# design1.net
KiCad netlist of a schematic drawn in EAGLE
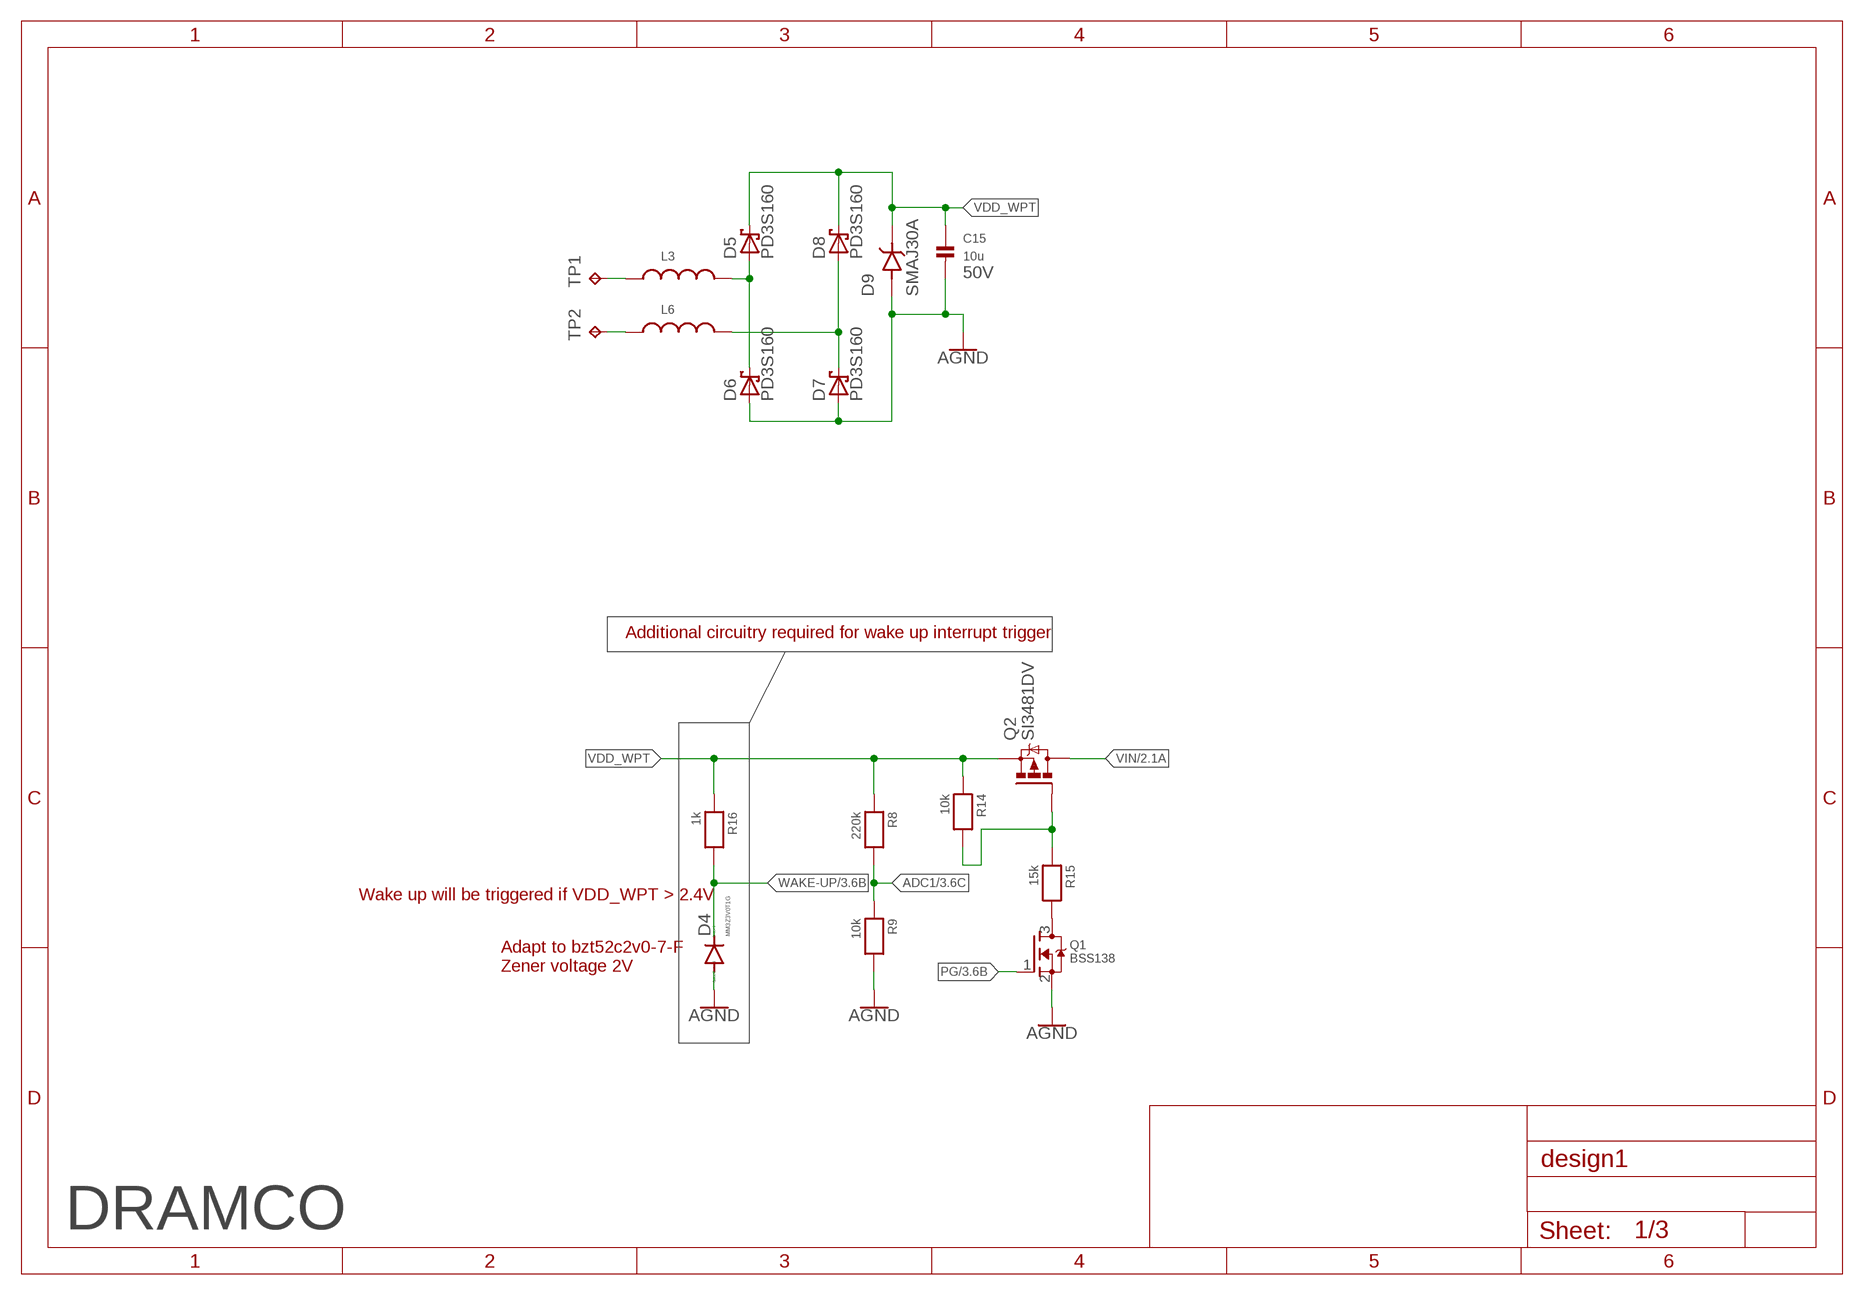
[diagram p0: schematic, sheet 1]
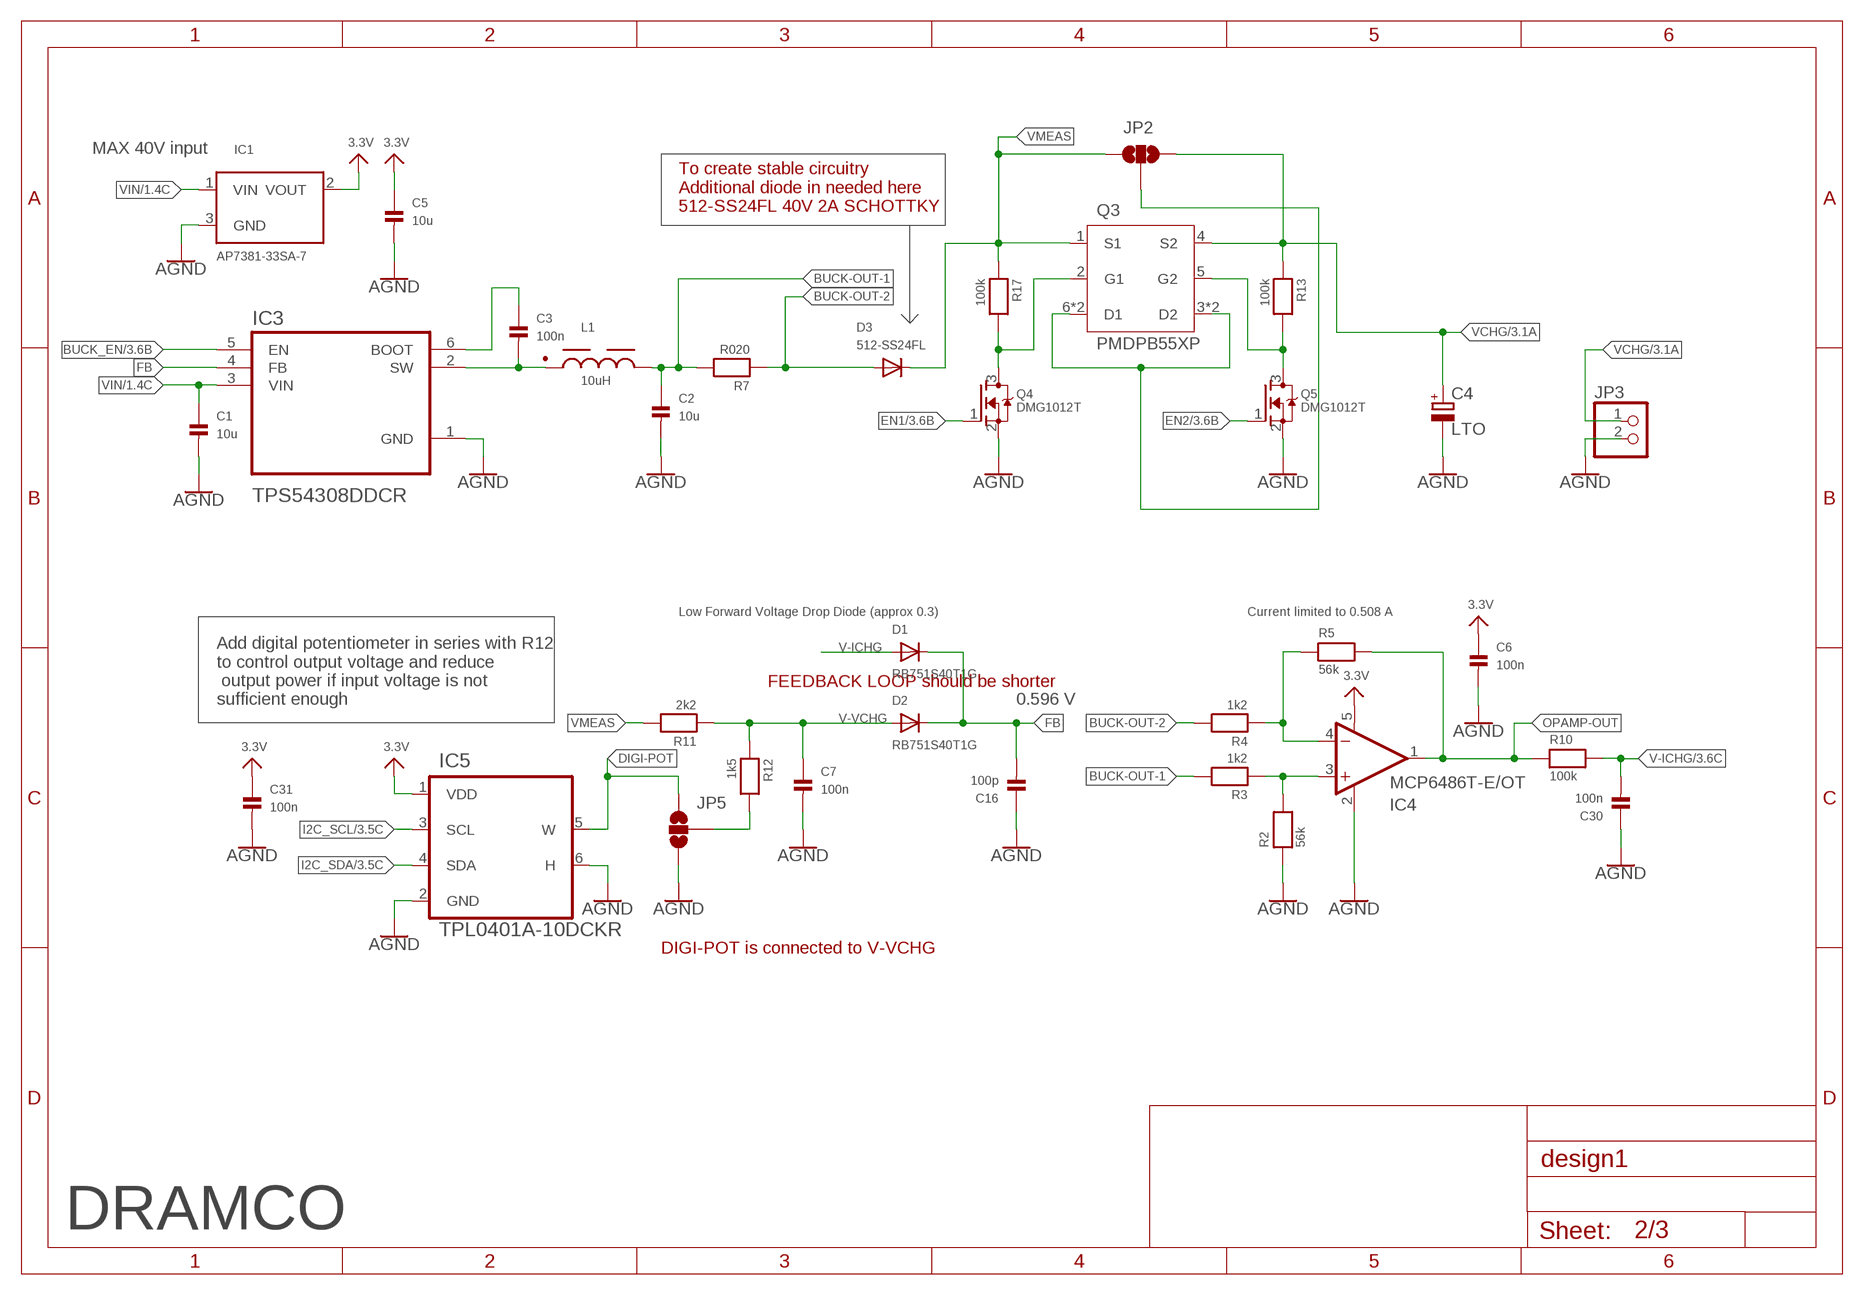
[diagram p1: schematic, sheet 2]
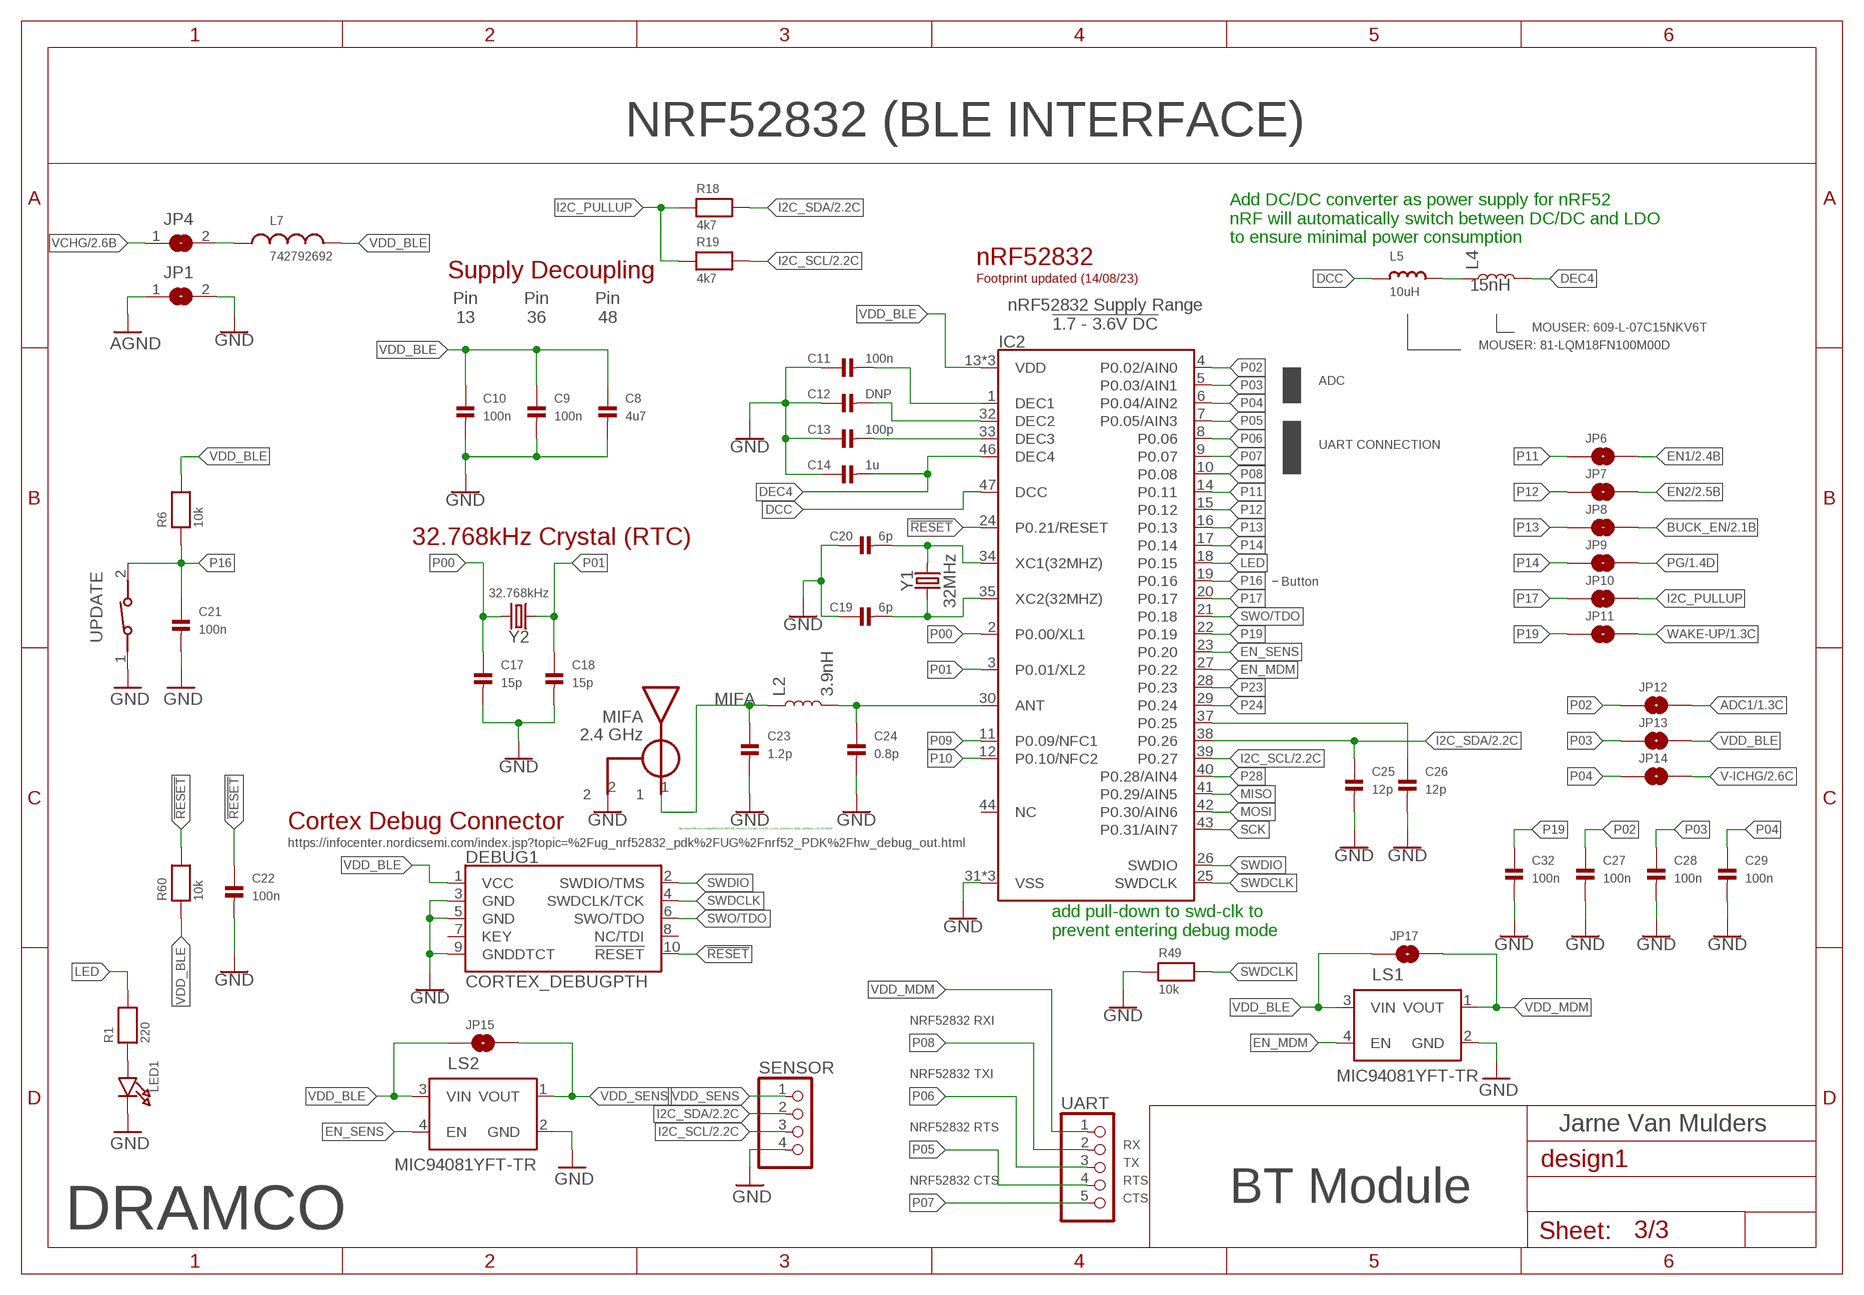
[diagram p2: schematic, sheet 3]

(export (version "E")
  (design (tool "Eeschema 10.0.6"))
  (components
    (comp (ref "C15")
      (value "10u")
      (footprint "eagle-import:1206")
      (libsource (lib "eagle-import") (part "CAP_CERAMIC1206"))
    )
    (comp (ref "D4")
      (value "MM3Z3V0T1G")
      (footprint "eagle-import:SOD323-R")
      (libsource (lib "eagle-import") (part "DIODE-SOD323-R"))
    )
    (comp (ref "D5")
      (value "PD3S160")
      (footprint "eagle-import:POWERDI323")
      (libsource (lib "eagle-import") (part "PD3S160"))
    )
    (comp (ref "D6")
      (value "PD3S160")
      (footprint "eagle-import:POWERDI323")
      (libsource (lib "eagle-import") (part "PD3S160"))
    )
    (comp (ref "D7")
      (value "PD3S160")
      (footprint "eagle-import:POWERDI323")
      (libsource (lib "eagle-import") (part "PD3S160"))
    )
    (comp (ref "D8")
      (value "PD3S160")
      (footprint "eagle-import:POWERDI323")
      (libsource (lib "eagle-import") (part "PD3S160"))
    )
    (comp (ref "D9")
      (value "SMAJ30A")
      (footprint "eagle-import:DIOM5026X229N")
      (fields (field (name "MF") "Littelfuse"))
      (libsource (lib "eagle-import") (part "SMAJ30A"))
    )
    (comp (ref "L3")
      (value "WE-CAIR_4248_744912182")
      (footprint "eagle-import:WE-CAIR_4248")
      (libsource (lib "eagle-import") (part "WE-CAIR_4248_744912182"))
    )
    (comp (ref "L6")
      (value "WE-CAIR_4248_744912182")
      (footprint "eagle-import:WE-CAIR_4248")
      (libsource (lib "eagle-import") (part "WE-CAIR_4248_744912182"))
    )
    (comp (ref "Q1")
      (value "BSS138")
      (footprint "eagle-import:SOT23-R")
      (libsource (lib "eagle-import") (part "MOSFET-NREFLOW"))
    )
    (comp (ref "Q2")
      (value "SI3481DV")
      (footprint "eagle-import:TSOP-6.PAC")
      (libsource (lib "eagle-import") (part "SI3481DV"))
    )
    (comp (ref "R8")
      (value "220k")
      (footprint "eagle-import:0603")
      (libsource (lib "eagle-import") (part "RESISTOR0603"))
    )
    (comp (ref "R9")
      (value "10k")
      (footprint "eagle-import:0603")
      (libsource (lib "eagle-import") (part "RESISTOR0603"))
    )
    (comp (ref "R14")
      (value "10k")
      (footprint "eagle-import:0603")
      (libsource (lib "eagle-import") (part "RESISTOR0603"))
    )
    (comp (ref "R15")
      (value "15k")
      (footprint "eagle-import:0603")
      (libsource (lib "eagle-import") (part "RESISTOR0603"))
    )
    (comp (ref "R16")
      (value "1k")
      (footprint "eagle-import:0603")
      (libsource (lib "eagle-import") (part "RESISTOR0603"))
    )
    (comp (ref "TP1")
      (value "TPTP20SQ")
      (footprint "eagle-import:TP20SQ")
      (libsource (lib "eagle-import") (part "TPTP20SQ"))
    )
    (comp (ref "TP2")
      (value "TPTP20SQ")
      (footprint "eagle-import:TP20SQ")
      (libsource (lib "eagle-import") (part "TPTP20SQ"))
    )
    (comp (ref "C1")
      (value "10u")
      (footprint "eagle-import:0603")
      (libsource (lib "eagle-import") (part "CAP_CERAMIC0603"))
    )
    (comp (ref "C2")
      (value "10u")
      (footprint "eagle-import:0603")
      (libsource (lib "eagle-import") (part "CAP_CERAMIC0603"))
    )
    (comp (ref "C3")
      (value "100n")
      (footprint "eagle-import:0603")
      (libsource (lib "eagle-import") (part "CAP_CERAMIC0603"))
    )
    (comp (ref "C4")
      (value "LTO")
      (footprint "eagle-import:E5-10,5")
      (libsource (lib "eagle-import") (part "CPOL-EUE5-10.5"))
    )
    (comp (ref "C5")
      (value "10u")
      (footprint "eagle-import:0603")
      (libsource (lib "eagle-import") (part "CAP_CERAMIC0603"))
    )
    (comp (ref "C6")
      (value "100n")
      (footprint "eagle-import:0402")
      (libsource (lib "eagle-import") (part "CAP_CERAMIC0402"))
    )
    (comp (ref "C7")
      (value "100n")
      (footprint "eagle-import:0603")
      (libsource (lib "eagle-import") (part "CAP_CERAMIC0603"))
    )
    (comp (ref "C16")
      (value "100p")
      (footprint "eagle-import:0603")
      (libsource (lib "eagle-import") (part "CAP_CERAMIC0603"))
    )
    (comp (ref "C30")
      (value "100n")
      (footprint "eagle-import:0603")
      (libsource (lib "eagle-import") (part "CAP_CERAMIC0603"))
    )
    (comp (ref "C31")
      (value "100n")
      (footprint "eagle-import:0402")
      (libsource (lib "eagle-import") (part "CAP_CERAMIC0402"))
    )
    (comp (ref "D1")
      (value "RB751S40T1G")
      (footprint "eagle-import:SOD-523")
      (libsource (lib "eagle-import") (part "DIODESOD-523"))
    )
    (comp (ref "D2")
      (value "RB751S40T1G")
      (footprint "eagle-import:SOD-523")
      (libsource (lib "eagle-import") (part "DIODESOD-523"))
    )
    (comp (ref "D3")
      (value "512-SS24FL")
      (footprint "eagle-import:SOD-123")
      (libsource (lib "eagle-import") (part "DIODESOD-123"))
    )
    (comp (ref "IC1")
      (value "AP7381-33SA-7")
      (footprint "eagle-import:SOT23-R")
      (libsource (lib "eagle-import") (part "VREG_SOT23"))
    )
    (comp (ref "IC3")
      (value "TPS54308DDCR")
      (footprint "eagle-import:SOT95P280X110-6N")
      (fields (field (name "MF") "Texas Instruments"))
      (libsource (lib "eagle-import") (part "TPS54308DDCR"))
    )
    (comp (ref "IC4")
      (value "MCP6486T-E/OT")
      (footprint "eagle-import:SOT23-5")
      (libsource (lib "eagle-import") (part "MCP6291T-E/OT"))
    )
    (comp (ref "IC5")
      (value "TPL0401A-10DCKR")
      (footprint "eagle-import:SOT65P210X110-6N")
      (fields (field (name "MF") "Texas Instruments"))
      (libsource (lib "eagle-import") (part "TPL0401A-10DCKR"))
    )
    (comp (ref "JP2")
      (value "JUMPER-SMT_3_NO_NO-SILK")
      (footprint "eagle-import:SMT-JUMPER_3_NO_NO-SILK")
      (libsource (lib "eagle-import") (part "JUMPER-SMT_3_NO_NO-SILK"))
    )
    (comp (ref "JP3")
      (value "HEADER-1X2ROUND")
      (footprint "eagle-import:1X02_ROUND")
      (libsource (lib "eagle-import") (part "HEADER-1X2ROUND"))
    )
    (comp (ref "JP5")
      (value "JUMPER-SMT_3_NO_NO-SILK")
      (footprint "eagle-import:SMT-JUMPER_3_NO_NO-SILK")
      (libsource (lib "eagle-import") (part "JUMPER-SMT_3_NO_NO-SILK"))
    )
    (comp (ref "L1")
      (value "10uH")
      (footprint "eagle-import:WE-PD_7332_7345_PLASTIC_BASE")
      (libsource (lib "eagle-import") (part "WE-PD_7332_PLASTIC_7447789127"))
    )
    (comp (ref "Q3")
      (value "PMDPB55XP")
      (footprint "eagle-import:SON65P200X200X65-8N")
      (libsource (lib "eagle-import") (part "PMDPB55XP"))
    )
    (comp (ref "Q4")
      (value "DMG1012T")
      (footprint "eagle-import:SOT523-3")
      (libsource (lib "eagle-import") (part "DMG1012T"))
    )
    (comp (ref "Q5")
      (value "DMG1012T")
      (footprint "eagle-import:SOT523-3")
      (libsource (lib "eagle-import") (part "DMG1012T"))
    )
    (comp (ref "R2")
      (value "56k")
      (footprint "eagle-import:0603")
      (libsource (lib "eagle-import") (part "RESISTOR0603"))
    )
    (comp (ref "R3")
      (value "1k2")
      (footprint "eagle-import:0603")
      (libsource (lib "eagle-import") (part "RESISTOR0603"))
    )
    (comp (ref "R4")
      (value "1k2")
      (footprint "eagle-import:0603")
      (libsource (lib "eagle-import") (part "RESISTOR0603"))
    )
    (comp (ref "R5")
      (value "56k")
      (footprint "eagle-import:0603")
      (libsource (lib "eagle-import") (part "RESISTOR0603"))
    )
    (comp (ref "R7")
      (value "R020")
      (footprint "eagle-import:0603")
      (libsource (lib "eagle-import") (part "RESISTOR0603"))
    )
    (comp (ref "R10")
      (value "100k")
      (footprint "eagle-import:0603")
      (libsource (lib "eagle-import") (part "RESISTOR0603"))
    )
    (comp (ref "R11")
      (value "2k2")
      (footprint "eagle-import:0603")
      (libsource (lib "eagle-import") (part "RESISTOR0603"))
    )
    (comp (ref "R12")
      (value "1k5")
      (footprint "eagle-import:0603")
      (libsource (lib "eagle-import") (part "RESISTOR0603"))
    )
    (comp (ref "R13")
      (value "100k")
      (footprint "eagle-import:0402")
      (libsource (lib "eagle-import") (part "RESISTOR0402"))
    )
    (comp (ref "R17")
      (value "100k")
      (footprint "eagle-import:0402")
      (libsource (lib "eagle-import") (part "RESISTOR0402"))
    )
    (comp (ref "C8")
      (value "4u7")
      (footprint "eagle-import:0603")
      (libsource (lib "eagle-import") (part "CAP_CERAMIC0603"))
    )
    (comp (ref "C9")
      (value "100n")
      (footprint "eagle-import:0402")
      (libsource (lib "eagle-import") (part "CAP_CERAMIC0402"))
    )
    (comp (ref "C10")
      (value "100n")
      (footprint "eagle-import:0402")
      (libsource (lib "eagle-import") (part "CAP_CERAMIC0402"))
    )
    (comp (ref "C11")
      (value "100n")
      (footprint "eagle-import:0402")
      (libsource (lib "eagle-import") (part "CAP_CERAMIC0402"))
    )
    (comp (ref "C12")
      (value "DNP")
      (footprint "eagle-import:0402")
      (libsource (lib "eagle-import") (part "CAP_CERAMIC0402"))
    )
    (comp (ref "C13")
      (value "100p")
      (footprint "eagle-import:0402")
      (libsource (lib "eagle-import") (part "CAP_CERAMIC0402"))
    )
    (comp (ref "C14")
      (value "1u")
      (footprint "eagle-import:0402")
      (libsource (lib "eagle-import") (part "CAP_CERAMIC0402"))
    )
    (comp (ref "C17")
      (value "15p")
      (footprint "eagle-import:0402")
      (libsource (lib "eagle-import") (part "CAP_CERAMIC0402"))
    )
    (comp (ref "C18")
      (value "15p")
      (footprint "eagle-import:0402")
      (libsource (lib "eagle-import") (part "CAP_CERAMIC0402"))
    )
    (comp (ref "C19")
      (value "6p")
      (footprint "eagle-import:0402")
      (libsource (lib "eagle-import") (part "CAP_CERAMIC0402"))
    )
    (comp (ref "C20")
      (value "6p")
      (footprint "eagle-import:0402")
      (libsource (lib "eagle-import") (part "CAP_CERAMIC0402"))
    )
    (comp (ref "C21")
      (value "100n")
      (footprint "eagle-import:0402")
      (libsource (lib "eagle-import") (part "CAP_CERAMIC0402"))
    )
    (comp (ref "C22")
      (value "100n")
      (footprint "eagle-import:0402")
      (libsource (lib "eagle-import") (part "CAP_CERAMIC0402"))
    )
    (comp (ref "C23")
      (value "1.2p")
      (footprint "eagle-import:0402")
      (libsource (lib "eagle-import") (part "CAP_CERAMIC0402"))
    )
    (comp (ref "C24")
      (value "0.8p")
      (footprint "eagle-import:0402")
      (libsource (lib "eagle-import") (part "CAP_CERAMIC0402"))
    )
    (comp (ref "C25")
      (value "12p")
      (footprint "eagle-import:0402")
      (libsource (lib "eagle-import") (part "CAP_CERAMIC0402"))
    )
    (comp (ref "C26")
      (value "12p")
      (footprint "eagle-import:0402")
      (libsource (lib "eagle-import") (part "CAP_CERAMIC0402"))
    )
    (comp (ref "C27")
      (value "100n")
      (footprint "eagle-import:0402")
      (libsource (lib "eagle-import") (part "CAP_CERAMIC0402"))
    )
    (comp (ref "C28")
      (value "100n")
      (footprint "eagle-import:0402")
      (libsource (lib "eagle-import") (part "CAP_CERAMIC0402"))
    )
    (comp (ref "C29")
      (value "100n")
      (footprint "eagle-import:0402")
      (libsource (lib "eagle-import") (part "CAP_CERAMIC0402"))
    )
    (comp (ref "C32")
      (value "100n")
      (footprint "eagle-import:0402")
      (libsource (lib "eagle-import") (part "CAP_CERAMIC0402"))
    )
    (comp (ref "DEBUG1")
      (value "CORTEX_DEBUGPTH")
      (footprint "eagle-import:2X5-PTH-1.27MM")
      (libsource (lib "eagle-import") (part "CORTEX_DEBUGPTH"))
    )
    (comp (ref "IC2")
      (value "NRF52832-EXTENDED")
      (footprint "eagle-import:QFN48-6X6MM-EXTENDED")
      (libsource (lib "eagle-import") (part "NRF52832-EXTENDED"))
    )
    (comp (ref "JP1")
      (value "SOLDERJUMPERREFLOW_NOPASTE")
      (footprint "eagle-import:SOLDERJUMPER_REFLOW_NOPASTE")
      (libsource (lib "eagle-import") (part "SOLDERJUMPERREFLOW_NOPASTE"))
    )
    (comp (ref "JP4")
      (value "SOLDERJUMPERREFLOW_NOPASTE")
      (footprint "eagle-import:SOLDERJUMPER_REFLOW_NOPASTE")
      (libsource (lib "eagle-import") (part "SOLDERJUMPERREFLOW_NOPASTE"))
    )
    (comp (ref "JP6")
      (value "JUMPER-SMT_2_NO_NO-SILK")
      (footprint "eagle-import:SMT-JUMPER_2_NO_NO-SILK")
      (libsource (lib "eagle-import") (part "JUMPER-SMT_2_NO_NO-SILK"))
    )
    (comp (ref "JP7")
      (value "JUMPER-SMT_2_NO_NO-SILK")
      (footprint "eagle-import:SMT-JUMPER_2_NO_NO-SILK")
      (libsource (lib "eagle-import") (part "JUMPER-SMT_2_NO_NO-SILK"))
    )
    (comp (ref "JP8")
      (value "JUMPER-SMT_2_NO_NO-SILK")
      (footprint "eagle-import:SMT-JUMPER_2_NO_NO-SILK")
      (libsource (lib "eagle-import") (part "JUMPER-SMT_2_NO_NO-SILK"))
    )
    (comp (ref "JP9")
      (value "JUMPER-SMT_2_NO_NO-SILK")
      (footprint "eagle-import:SMT-JUMPER_2_NO_NO-SILK")
      (libsource (lib "eagle-import") (part "JUMPER-SMT_2_NO_NO-SILK"))
    )
    (comp (ref "JP10")
      (value "JUMPER-SMT_2_NO_NO-SILK")
      (footprint "eagle-import:SMT-JUMPER_2_NO_NO-SILK")
      (libsource (lib "eagle-import") (part "JUMPER-SMT_2_NO_NO-SILK"))
    )
    (comp (ref "JP11")
      (value "JUMPER-SMT_2_NO_NO-SILK")
      (footprint "eagle-import:SMT-JUMPER_2_NO_NO-SILK")
      (libsource (lib "eagle-import") (part "JUMPER-SMT_2_NO_NO-SILK"))
    )
    (comp (ref "JP12")
      (value "JUMPER-SMT_2_NO_NO-SILK")
      (footprint "eagle-import:SMT-JUMPER_2_NO_NO-SILK")
      (libsource (lib "eagle-import") (part "JUMPER-SMT_2_NO_NO-SILK"))
    )
    (comp (ref "JP13")
      (value "JUMPER-SMT_2_NO_NO-SILK")
      (footprint "eagle-import:SMT-JUMPER_2_NO_NO-SILK")
      (libsource (lib "eagle-import") (part "JUMPER-SMT_2_NO_NO-SILK"))
    )
    (comp (ref "JP14")
      (value "JUMPER-SMT_2_NO_NO-SILK")
      (footprint "eagle-import:SMT-JUMPER_2_NO_NO-SILK")
      (libsource (lib "eagle-import") (part "JUMPER-SMT_2_NO_NO-SILK"))
    )
    (comp (ref "JP15")
      (value "JUMPER-SMT_2_NO_NO-SILK")
      (footprint "eagle-import:SMT-JUMPER_2_NO_NO-SILK")
      (libsource (lib "eagle-import") (part "JUMPER-SMT_2_NO_NO-SILK"))
    )
    (comp (ref "JP17")
      (value "JUMPER-SMT_2_NO_NO-SILK")
      (footprint "eagle-import:SMT-JUMPER_2_NO_NO-SILK")
      (libsource (lib "eagle-import") (part "JUMPER-SMT_2_NO_NO-SILK"))
    )
    (comp (ref "L2")
      (value "3.9nH")
      (footprint "eagle-import:0402")
      (libsource (lib "eagle-import") (part "INDUCTOR-0402-3.9NH"))
    )
    (comp (ref "L4")
      (value "15nH")
      (footprint "eagle-import:0402")
      (libsource (lib "eagle-import") (part "INDUCTOR-0402-3.9NH"))
    )
    (comp (ref "L5")
      (value "10uH")
      (footprint "eagle-import:_0603MP")
      (libsource (lib "eagle-import") (part "INDUCTOR_0603MP"))
    )
    (comp (ref "L7")
      (value "742792692")
      (footprint "eagle-import:WE-CBF_0603(W=2.2)")
      (libsource (lib "eagle-import") (part "WE-CBF_0603_WB_HS_742792692"))
    )
    (comp (ref "LED1")
      (value "LED0805")
      (footprint "eagle-import:CHIPLED_0805")
      (libsource (lib "eagle-import") (part "LED0805"))
    )
    (comp (ref "LS1")
      (value "MIC94081YFT-TR")
      (footprint "eagle-import:IC_MIC94081YFT-TR")
      (fields (field (name "MF") "Microchip"))
      (libsource (lib "eagle-import") (part "MIC94081YFT-TR"))
    )
    (comp (ref "LS2")
      (value "MIC94081YFT-TR")
      (footprint "eagle-import:IC_MIC94081YFT-TR")
      (fields (field (name "MF") "Microchip"))
      (libsource (lib "eagle-import") (part "MIC94081YFT-TR"))
    )
    (comp (ref "R1")
      (value "220")
      (footprint "eagle-import:0603")
      (libsource (lib "eagle-import") (part "RESISTOR0603"))
    )
    (comp (ref "R6")
      (value "10k")
      (footprint "eagle-import:0402")
      (libsource (lib "eagle-import") (part "RESISTOR0402"))
    )
    (comp (ref "R18")
      (value "4k7")
      (footprint "eagle-import:0402")
      (libsource (lib "eagle-import") (part "RESISTOR0402"))
    )
    (comp (ref "R19")
      (value "4k7")
      (footprint "eagle-import:0402")
      (libsource (lib "eagle-import") (part "RESISTOR0402"))
    )
    (comp (ref "R49")
      (value "10k")
      (footprint "eagle-import:0402")
      (libsource (lib "eagle-import") (part "RESISTOR0402"))
    )
    (comp (ref "R60")
      (value "10k")
      (footprint "eagle-import:0402")
      (libsource (lib "eagle-import") (part "RESISTOR0402"))
    )
    (comp (ref "SENSOR")
      (value "HEADER-1X4ROUND")
      (footprint "eagle-import:1X04_ROUND")
      (libsource (lib "eagle-import") (part "HEADER-1X4ROUND"))
    )
    (comp (ref "U$18")
      (value "BLE-ANT")
      (footprint "eagle-import:ANT-2G4")
      (libsource (lib "eagle-import") (part "BLE-ANT"))
    )
    (comp (ref "UART")
      (value "HEADER-1X5ROUND")
      (footprint "eagle-import:1X05_ROUND")
      (libsource (lib "eagle-import") (part "HEADER-1X5ROUND"))
    )
    (comp (ref "UPDATE")
      (value "434111043826")
      (footprint "eagle-import:434111043826")
      (libsource (lib "eagle-import") (part "434111043826"))
    )
    (comp (ref "Y1")
      (value "32MHz")
      (footprint "eagle-import:CRYSTAL-SMD-2.0X1.6MM")
      (libsource (lib "eagle-import") (part "CRYSTAL-32MHZ-SMD-2.0X1.6MM"))
    )
    (comp (ref "Y2")
      (value "32.768kHz")
      (footprint "eagle-import:CRYSTAL-SMD-3.2X1.5MM")
      (libsource (lib "eagle-import") (part "CRYSTAL-32.768KHZSMD-3.2X1.5"))
    )
  )
  (nets
    (net (code "1") (name "3.3V") (class "Default")
      (node (ref "C31") (pin "1") (pinfunction "P$1_1") (pintype "passive"))
      (node (ref "C5") (pin "1") (pinfunction "P$1_1") (pintype "passive"))
      (node (ref "C6") (pin "1") (pinfunction "P$1_1") (pintype "passive"))
      (node (ref "IC1") (pin "2") (pinfunction "VOUT_2") (pintype "power_in"))
      (node (ref "IC4") (pin "5") (pinfunction "V+_5") (pintype "power_in"))
      (node (ref "IC5") (pin "1") (pinfunction "VDD_1") (pintype "power_in"))
    )
    (net (code "2") (name "ADC1") (class "Default")
      (node (ref "JP12") (pin "2") (pinfunction "2_2") (pintype "passive"))
      (node (ref "R8") (pin "2") (pinfunction "2_2") (pintype "passive"))
      (node (ref "R9") (pin "1") (pinfunction "1_1") (pintype "passive"))
    )
    (net (code "3") (name "AGND") (class "Default")
      (node (ref "C1") (pin "2") (pinfunction "P$2_2") (pintype "passive"))
      (node (ref "C15") (pin "2") (pinfunction "P$2_2") (pintype "passive"))
      (node (ref "C16") (pin "1") (pinfunction "P$1_1") (pintype "passive"))
      (node (ref "C2") (pin "2") (pinfunction "P$2_2") (pintype "passive"))
      (node (ref "C30") (pin "1") (pinfunction "P$1_1") (pintype "passive"))
      (node (ref "C31") (pin "2") (pinfunction "P$2_2") (pintype "passive"))
      (node (ref "C4") (pin "-") (pinfunction "-_-") (pintype "passive"))
      (node (ref "C5") (pin "2") (pinfunction "P$2_2") (pintype "passive"))
      (node (ref "C6") (pin "2") (pinfunction "P$2_2") (pintype "passive"))
      (node (ref "C7") (pin "2") (pinfunction "P$2_2") (pintype "passive"))
      (node (ref "D4") (pin "A") (pinfunction "A_A") (pintype "passive"))
      (node (ref "D6") (pin "A") (pinfunction "A_A") (pintype "passive"))
      (node (ref "D7") (pin "A") (pinfunction "A_A") (pintype "passive"))
      (node (ref "D9") (pin "A") (pinfunction "A_A") (pintype "passive"))
      (node (ref "IC1") (pin "3") (pinfunction "GND_3") (pintype "power_in"))
      (node (ref "IC3") (pin "1") (pinfunction "GND_1") (pintype "power_in"))
      (node (ref "IC4") (pin "2") (pinfunction "V-_2") (pintype "power_in"))
      (node (ref "IC5") (pin "2") (pinfunction "GND_2") (pintype "power_in"))
      (node (ref "IC5") (pin "6") (pinfunction "H_6") (pintype "bidirectional"))
      (node (ref "JP1") (pin "1") (pinfunction "1_1") (pintype "passive"))
      (node (ref "JP3") (pin "2") (pinfunction "2_2") (pintype "passive"))
      (node (ref "JP5") (pin "1") (pinfunction "1_1") (pintype "passive"))
      (node (ref "Q1") (pin "2") (pinfunction "S_2") (pintype "bidirectional"))
      (node (ref "Q4") (pin "2") (pinfunction "S_2") (pintype "bidirectional"))
      (node (ref "Q5") (pin "2") (pinfunction "S_2") (pintype "bidirectional"))
      (node (ref "R2") (pin "1") (pinfunction "1_1") (pintype "passive"))
      (node (ref "R9") (pin "2") (pinfunction "2_2") (pintype "passive"))
    )
    (net (code "4") (name "BUCK-OUT-1") (class "Default")
      (node (ref "C2") (pin "1") (pinfunction "P$1_1") (pintype "passive"))
      (node (ref "L1") (pin "2") (pinfunction "2_2") (pintype "passive"))
      (node (ref "R3") (pin "2") (pinfunction "2_2") (pintype "passive"))
      (node (ref "R7") (pin "2") (pinfunction "2_2") (pintype "passive"))
    )
    (net (code "5") (name "BUCK-OUT-2") (class "Default")
      (node (ref "D3") (pin "A") (pinfunction "A_A") (pintype "passive"))
      (node (ref "R4") (pin "2") (pinfunction "2_2") (pintype "passive"))
      (node (ref "R7") (pin "1") (pinfunction "1_1") (pintype "passive"))
    )
    (net (code "6") (name "BUCK_EN") (class "Default")
      (node (ref "IC3") (pin "5") (pinfunction "EN_5") (pintype "input"))
      (node (ref "JP8") (pin "2") (pinfunction "2_2") (pintype "passive"))
    )
    (net (code "7") (name "DCC") (class "Default")
      (node (ref "IC2") (pin "47") (pinfunction "DCC_47") (pintype "bidirectional"))
      (node (ref "L5") (pin "1") (pinfunction "1_1") (pintype "passive"))
    )
    (net (code "8") (name "DEC4") (class "Default")
      (node (ref "C14") (pin "2") (pinfunction "P$2_2") (pintype "passive"))
      (node (ref "IC2") (pin "46") (pinfunction "DEC4_46") (pintype "bidirectional"))
      (node (ref "L4") (pin "2") (pinfunction "2_2") (pintype "passive"))
    )
    (net (code "9") (name "DIGI-POT") (class "Default")
      (node (ref "IC5") (pin "5") (pinfunction "W_5") (pintype "bidirectional"))
      (node (ref "JP5") (pin "3") (pinfunction "3_3") (pintype "passive"))
    )
    (net (code "10") (name "EN1") (class "Default")
      (node (ref "JP6") (pin "2") (pinfunction "2_2") (pintype "passive"))
      (node (ref "Q4") (pin "1") (pinfunction "G_1") (pintype "bidirectional"))
    )
    (net (code "11") (name "EN2") (class "Default")
      (node (ref "JP7") (pin "2") (pinfunction "2_2") (pintype "passive"))
      (node (ref "Q5") (pin "1") (pinfunction "G_1") (pintype "bidirectional"))
    )
    (net (code "12") (name "EN_MDM") (class "Default")
      (node (ref "IC2") (pin "27") (pinfunction "P0.22_27") (pintype "bidirectional"))
      (node (ref "LS1") (pin "4") (pinfunction "EN_4") (pintype "input"))
    )
    (net (code "13") (name "EN_SENS") (class "Default")
      (node (ref "IC2") (pin "23") (pinfunction "P0.20_23") (pintype "bidirectional"))
      (node (ref "LS2") (pin "4") (pinfunction "EN_4") (pintype "input"))
    )
    (net (code "14") (name "FB") (class "Default")
      (node (ref "C16") (pin "2") (pinfunction "P$2_2") (pintype "passive"))
      (node (ref "D1") (pin "K") (pinfunction "C_K") (pintype "passive"))
      (node (ref "D2") (pin "K") (pinfunction "C_K") (pintype "passive"))
      (node (ref "IC3") (pin "4") (pinfunction "FB_4") (pintype "input"))
    )
    (net (code "15") (name "GND") (class "Default")
      (node (ref "C10") (pin "2") (pinfunction "P$2_2") (pintype "passive"))
      (node (ref "C11") (pin "1") (pinfunction "P$1_1") (pintype "passive"))
      (node (ref "C12") (pin "1") (pinfunction "P$1_1") (pintype "passive"))
      (node (ref "C13") (pin "1") (pinfunction "P$1_1") (pintype "passive"))
      (node (ref "C14") (pin "1") (pinfunction "P$1_1") (pintype "passive"))
      (node (ref "C17") (pin "2") (pinfunction "P$2_2") (pintype "passive"))
      (node (ref "C18") (pin "2") (pinfunction "P$2_2") (pintype "passive"))
      (node (ref "C19") (pin "1") (pinfunction "P$1_1") (pintype "passive"))
      (node (ref "C20") (pin "1") (pinfunction "P$1_1") (pintype "passive"))
      (node (ref "C21") (pin "2") (pinfunction "P$2_2") (pintype "passive"))
      (node (ref "C22") (pin "2") (pinfunction "P$2_2") (pintype "passive"))
      (node (ref "C23") (pin "2") (pinfunction "P$2_2") (pintype "passive"))
      (node (ref "C24") (pin "2") (pinfunction "P$2_2") (pintype "passive"))
      (node (ref "C25") (pin "2") (pinfunction "P$2_2") (pintype "passive"))
      (node (ref "C26") (pin "2") (pinfunction "P$2_2") (pintype "passive"))
      (node (ref "C27") (pin "2") (pinfunction "P$2_2") (pintype "passive"))
      (node (ref "C28") (pin "2") (pinfunction "P$2_2") (pintype "passive"))
      (node (ref "C29") (pin "2") (pinfunction "P$2_2") (pintype "passive"))
      (node (ref "C32") (pin "2") (pinfunction "P$2_2") (pintype "passive"))
      (node (ref "C8") (pin "2") (pinfunction "P$2_2") (pintype "passive"))
      (node (ref "C9") (pin "2") (pinfunction "P$2_2") (pintype "passive"))
      (node (ref "DEBUG1") (pin "3") (pinfunction "GND_3") (pintype "bidirectional"))
      (node (ref "DEBUG1") (pin "5") (pinfunction "GND_5") (pintype "bidirectional"))
      (node (ref "DEBUG1") (pin "9") (pinfunction "GNDDTCT_9") (pintype "bidirectional"))
      (node (ref "IC2") (pin "31") (pinfunction "VSS_31") (pintype "bidirectional"))
      (node (ref "IC2") (pin "45") (pinfunction "VSS_45") (pintype "bidirectional"))
      (node (ref "IC2") (pin "EP") (pinfunction "VSS_EP") (pintype "bidirectional"))
      (node (ref "JP1") (pin "2") (pinfunction "2_2") (pintype "passive"))
      (node (ref "LED1") (pin "C") (pinfunction "C_C") (pintype "passive"))
      (node (ref "LS1") (pin "2") (pinfunction "GND_2") (pintype "power_in"))
      (node (ref "LS2") (pin "2") (pinfunction "GND_2") (pintype "power_in"))
      (node (ref "R49") (pin "1") (pinfunction "1_1") (pintype "passive"))
      (node (ref "SENSOR") (pin "4") (pinfunction "4_4") (pintype "passive"))
      (node (ref "U$18") (pin "2") (pinfunction "2_2") (pintype "bidirectional"))
      (node (ref "UPDATE") (pin "1") (pinfunction "1_1") (pintype "passive"))
    )
    (net (code "16") (name "I2C_PULLUP") (class "Default")
      (node (ref "JP10") (pin "2") (pinfunction "2_2") (pintype "passive"))
      (node (ref "R18") (pin "1") (pinfunction "1_1") (pintype "passive"))
      (node (ref "R19") (pin "1") (pinfunction "1_1") (pintype "passive"))
    )
    (net (code "17") (name "I2C_SCL") (class "Default")
      (node (ref "IC2") (pin "39") (pinfunction "P0.27_39") (pintype "bidirectional"))
      (node (ref "IC5") (pin "3") (pinfunction "SCL_3") (pintype "bidirectional"))
      (node (ref "R19") (pin "2") (pinfunction "2_2") (pintype "passive"))
      (node (ref "SENSOR") (pin "3") (pinfunction "3_3") (pintype "passive"))
    )
    (net (code "18") (name "I2C_SDA") (class "Default")
      (node (ref "C25") (pin "1") (pinfunction "P$1_1") (pintype "passive"))
      (node (ref "IC2") (pin "38") (pinfunction "P0.26_38") (pintype "bidirectional"))
      (node (ref "IC5") (pin "4") (pinfunction "SDA_4") (pintype "bidirectional"))
      (node (ref "R18") (pin "2") (pinfunction "2_2") (pintype "passive"))
      (node (ref "SENSOR") (pin "2") (pinfunction "2_2") (pintype "passive"))
    )
    (net (code "19") (name "LED") (class "Default")
      (node (ref "IC2") (pin "18") (pinfunction "P0.15_18") (pintype "bidirectional"))
      (node (ref "R1") (pin "2") (pinfunction "2_2") (pintype "passive"))
    )
    (net (code "20") (name "MIFA") (class "Default")
      (node (ref "C23") (pin "1") (pinfunction "P$1_1") (pintype "passive"))
      (node (ref "L2") (pin "1") (pinfunction "1_1") (pintype "passive"))
      (node (ref "U$18") (pin "1") (pinfunction "1_1") (pintype "bidirectional"))
    )
    (net (code "21") (name "MISO") (class "Default")
      (node (ref "IC2") (pin "41") (pinfunction "P0.29/AIN5_41") (pintype "bidirectional"))
    )
    (net (code "22") (name "MOSI") (class "Default")
      (node (ref "IC2") (pin "42") (pinfunction "P0.30/AIN6_42") (pintype "bidirectional"))
    )
    (net (code "23") (name "Net-(C3-P$1)") (class "Default")
      (node (ref "C3") (pin "1") (pinfunction "P$1_1") (pintype "passive"))
      (node (ref "IC3") (pin "6") (pinfunction "BOOT_6") (pintype "output"))
    )
    (net (code "24") (name "Net-(C3-P$2)") (class "Default")
      (node (ref "C3") (pin "2") (pinfunction "P$2_2") (pintype "passive"))
      (node (ref "IC3") (pin "2") (pinfunction "SW_2") (pintype "output"))
      (node (ref "L1") (pin "1") (pinfunction "1_1") (pintype "passive"))
    )
    (net (code "25") (name "Net-(C11-P$2)") (class "Default")
      (node (ref "C11") (pin "2") (pinfunction "P$2_2") (pintype "passive"))
      (node (ref "IC2") (pin "1") (pinfunction "DEC1_1") (pintype "bidirectional"))
    )
    (net (code "26") (name "Net-(C12-P$2)") (class "Default")
      (node (ref "C12") (pin "2") (pinfunction "P$2_2") (pintype "passive"))
      (node (ref "IC2") (pin "32") (pinfunction "DEC2_32") (pintype "bidirectional"))
    )
    (net (code "27") (name "Net-(C13-P$2)") (class "Default")
      (node (ref "C13") (pin "2") (pinfunction "P$2_2") (pintype "passive"))
      (node (ref "IC2") (pin "33") (pinfunction "DEC3_33") (pintype "bidirectional"))
    )
    (net (code "28") (name "Net-(C19-P$2)") (class "Default")
      (node (ref "C19") (pin "2") (pinfunction "P$2_2") (pintype "passive"))
      (node (ref "IC2") (pin "35") (pinfunction "XC2(32MHZ)_35") (pintype "bidirectional"))
      (node (ref "Y1") (pin "1") (pinfunction "1_1") (pintype "passive"))
    )
    (net (code "29") (name "Net-(C20-P$2)") (class "Default")
      (node (ref "C20") (pin "2") (pinfunction "P$2_2") (pintype "passive"))
      (node (ref "IC2") (pin "34") (pinfunction "XC1(32MHZ)_34") (pintype "bidirectional"))
      (node (ref "Y1") (pin "3") (pinfunction "2_3") (pintype "passive"))
    )
    (net (code "30") (name "Net-(C24-P$1)") (class "Default")
      (node (ref "C24") (pin "1") (pinfunction "P$1_1") (pintype "passive"))
      (node (ref "IC2") (pin "30") (pinfunction "ANT_30") (pintype "bidirectional"))
      (node (ref "L2") (pin "2") (pinfunction "2_2") (pintype "passive"))
    )
    (net (code "31") (name "Net-(C26-P$1)") (class "Default")
      (node (ref "C26") (pin "1") (pinfunction "P$1_1") (pintype "passive"))
      (node (ref "IC2") (pin "37") (pinfunction "P0.25_37") (pintype "bidirectional"))
    )
    (net (code "32") (name "Net-(D5-PadA)") (class "Default")
      (node (ref "D5") (pin "A") (pinfunction "A_A") (pintype "passive"))
      (node (ref "D6") (pin "C") (pinfunction "C_C") (pintype "passive"))
      (node (ref "L3") (pin "2") (pinfunction "2_2") (pintype "passive"))
    )
    (net (code "33") (name "Net-(D7-PadC)") (class "Default")
      (node (ref "D7") (pin "C") (pinfunction "C_C") (pintype "passive"))
      (node (ref "D8") (pin "A") (pinfunction "A_A") (pintype "passive"))
      (node (ref "L6") (pin "2") (pinfunction "2_2") (pintype "passive"))
    )
    (net (code "34") (name "Net-(IC4-+IN)") (class "Default")
      (node (ref "IC4") (pin "3") (pinfunction "+IN_3") (pintype "input"))
      (node (ref "R2") (pin "2") (pinfunction "2_2") (pintype "passive"))
      (node (ref "R3") (pin "1") (pinfunction "1_1") (pintype "passive"))
    )
    (net (code "35") (name "Net-(IC4--IN)") (class "Default")
      (node (ref "IC4") (pin "4") (pinfunction "-IN_4") (pintype "input"))
      (node (ref "R4") (pin "1") (pinfunction "1_1") (pintype "passive"))
      (node (ref "R5") (pin "1") (pinfunction "1_1") (pintype "passive"))
    )
    (net (code "36") (name "Net-(JP2-Pad2)") (class "Default")
      (node (ref "JP2") (pin "2") (pinfunction "2_2") (pintype "passive"))
      (node (ref "Q3") (pin "3") (pinfunction "D2_3") (pintype "bidirectional"))
      (node (ref "Q3") (pin "6") (pinfunction "D1_6") (pintype "bidirectional"))
      (node (ref "Q3") (pin "7") (pinfunction "D1_7") (pintype "bidirectional"))
      (node (ref "Q3") (pin "8") (pinfunction "D2_8") (pintype "bidirectional"))
    )
    (net (code "37") (name "Net-(JP4-Pad2)") (class "Default")
      (node (ref "JP4") (pin "2") (pinfunction "2_2") (pintype "passive"))
      (node (ref "L7") (pin "1") (pinfunction "1_1") (pintype "passive"))
    )
    (net (code "38") (name "Net-(JP5-Pad2)") (class "Default")
      (node (ref "JP5") (pin "2") (pinfunction "2_2") (pintype "passive"))
      (node (ref "R12") (pin "2") (pinfunction "2_2") (pintype "passive"))
    )
    (net (code "39") (name "Net-(L3-Pad1)") (class "Default")
      (node (ref "L3") (pin "1") (pinfunction "1_1") (pintype "passive"))
      (node (ref "TP1") (pin "TP") (pinfunction "TP_TP") (pintype "input"))
    )
    (net (code "40") (name "Net-(L4-Pad1)") (class "Default")
      (node (ref "L4") (pin "1") (pinfunction "1_1") (pintype "passive"))
      (node (ref "L5") (pin "2") (pinfunction "2_2") (pintype "passive"))
    )
    (net (code "41") (name "Net-(L6-Pad1)") (class "Default")
      (node (ref "L6") (pin "1") (pinfunction "1_1") (pintype "passive"))
      (node (ref "TP2") (pin "TP") (pinfunction "TP_TP") (pintype "input"))
    )
    (net (code "42") (name "Net-(LED1-PadA)") (class "Default")
      (node (ref "LED1") (pin "A") (pinfunction "A_A") (pintype "passive"))
      (node (ref "R1") (pin "1") (pinfunction "1_1") (pintype "passive"))
    )
    (net (code "43") (name "Net-(Q1-D)") (class "Default")
      (node (ref "Q1") (pin "3") (pinfunction "D_3") (pintype "bidirectional"))
      (node (ref "R15") (pin "2") (pinfunction "2_2") (pintype "passive"))
    )
    (net (code "44") (name "Net-(Q2-G)") (class "Default")
      (node (ref "Q2") (pin "3") (pinfunction "G_3") (pintype "passive"))
      (node (ref "R14") (pin "2") (pinfunction "2_2") (pintype "passive"))
      (node (ref "R15") (pin "1") (pinfunction "1_1") (pintype "passive"))
    )
    (net (code "45") (name "Net-(Q3-G1)") (class "Default")
      (node (ref "Q3") (pin "2") (pinfunction "G1_2") (pintype "bidirectional"))
      (node (ref "Q4") (pin "3") (pinfunction "D_3") (pintype "bidirectional"))
      (node (ref "R17") (pin "2") (pinfunction "2_2") (pintype "passive"))
    )
    (net (code "46") (name "Net-(Q3-G2)") (class "Default")
      (node (ref "Q3") (pin "5") (pinfunction "G2_5") (pintype "bidirectional"))
      (node (ref "Q5") (pin "3") (pinfunction "D_3") (pintype "bidirectional"))
      (node (ref "R13") (pin "2") (pinfunction "2_2") (pintype "passive"))
    )
    (net (code "47") (name "OPAMP-OUT") (class "Default")
      (node (ref "IC4") (pin "1") (pinfunction "OUT_1") (pintype "output"))
      (node (ref "R10") (pin "1") (pinfunction "1_1") (pintype "passive"))
      (node (ref "R5") (pin "2") (pinfunction "2_2") (pintype "passive"))
    )
    (net (code "48") (name "P00") (class "Default")
      (node (ref "C17") (pin "1") (pinfunction "P$1_1") (pintype "passive"))
      (node (ref "IC2") (pin "2") (pinfunction "P0.00/XL1_2") (pintype "bidirectional"))
      (node (ref "Y2") (pin "P$2") (pinfunction "2_P$2") (pintype "passive"))
    )
    (net (code "49") (name "P01") (class "Default")
      (node (ref "C18") (pin "1") (pinfunction "P$1_1") (pintype "passive"))
      (node (ref "IC2") (pin "3") (pinfunction "P0.01/XL2_3") (pintype "bidirectional"))
      (node (ref "Y2") (pin "P$1") (pinfunction "1_P$1") (pintype "passive"))
    )
    (net (code "50") (name "P02") (class "Default")
      (node (ref "C27") (pin "1") (pinfunction "P$1_1") (pintype "passive"))
      (node (ref "IC2") (pin "4") (pinfunction "P0.02/AIN0_4") (pintype "bidirectional"))
      (node (ref "JP12") (pin "1") (pinfunction "1_1") (pintype "passive"))
    )
    (net (code "51") (name "P03") (class "Default")
      (node (ref "C28") (pin "1") (pinfunction "P$1_1") (pintype "passive"))
      (node (ref "IC2") (pin "5") (pinfunction "P0.03/AIN1_5") (pintype "bidirectional"))
      (node (ref "JP13") (pin "1") (pinfunction "1_1") (pintype "passive"))
    )
    (net (code "52") (name "P04") (class "Default")
      (node (ref "C29") (pin "1") (pinfunction "P$1_1") (pintype "passive"))
      (node (ref "IC2") (pin "6") (pinfunction "P0.04/AIN2_6") (pintype "bidirectional"))
      (node (ref "JP14") (pin "1") (pinfunction "1_1") (pintype "passive"))
    )
    (net (code "53") (name "P05") (class "Default")
      (node (ref "IC2") (pin "7") (pinfunction "P0.05/AIN3_7") (pintype "bidirectional"))
      (node (ref "UART") (pin "4") (pinfunction "4_4") (pintype "passive"))
    )
    (net (code "54") (name "P06") (class "Default")
      (node (ref "IC2") (pin "8") (pinfunction "P0.06_8") (pintype "bidirectional"))
      (node (ref "UART") (pin "3") (pinfunction "3_3") (pintype "passive"))
    )
    (net (code "55") (name "P07") (class "Default")
      (node (ref "IC2") (pin "9") (pinfunction "P0.07_9") (pintype "bidirectional"))
      (node (ref "UART") (pin "5") (pinfunction "5_5") (pintype "passive"))
    )
    (net (code "56") (name "P08") (class "Default")
      (node (ref "IC2") (pin "10") (pinfunction "P0.08_10") (pintype "bidirectional"))
      (node (ref "UART") (pin "2") (pinfunction "2_2") (pintype "passive"))
    )
    (net (code "57") (name "P09") (class "Default")
      (node (ref "IC2") (pin "11") (pinfunction "P0.09/NFC1_11") (pintype "bidirectional"))
    )
    (net (code "58") (name "P10") (class "Default")
      (node (ref "IC2") (pin "12") (pinfunction "P0.10/NFC2_12") (pintype "bidirectional"))
    )
    (net (code "59") (name "P11") (class "Default")
      (node (ref "IC2") (pin "14") (pinfunction "P0.11_14") (pintype "bidirectional"))
      (node (ref "JP6") (pin "1") (pinfunction "1_1") (pintype "passive"))
    )
    (net (code "60") (name "P12") (class "Default")
      (node (ref "IC2") (pin "15") (pinfunction "P0.12_15") (pintype "bidirectional"))
      (node (ref "JP7") (pin "1") (pinfunction "1_1") (pintype "passive"))
    )
    (net (code "61") (name "P13") (class "Default")
      (node (ref "IC2") (pin "16") (pinfunction "P0.13_16") (pintype "bidirectional"))
      (node (ref "JP8") (pin "1") (pinfunction "1_1") (pintype "passive"))
    )
    (net (code "62") (name "P14") (class "Default")
      (node (ref "IC2") (pin "17") (pinfunction "P0.14_17") (pintype "bidirectional"))
      (node (ref "JP9") (pin "1") (pinfunction "1_1") (pintype "passive"))
    )
    (net (code "63") (name "P16") (class "Default")
      (node (ref "C21") (pin "1") (pinfunction "P$1_1") (pintype "passive"))
      (node (ref "IC2") (pin "19") (pinfunction "P0.16_19") (pintype "bidirectional"))
      (node (ref "R6") (pin "1") (pinfunction "1_1") (pintype "passive"))
      (node (ref "UPDATE") (pin "2") (pinfunction "2_2") (pintype "passive"))
    )
    (net (code "64") (name "P17") (class "Default")
      (node (ref "IC2") (pin "20") (pinfunction "P0.17_20") (pintype "bidirectional"))
      (node (ref "JP10") (pin "1") (pinfunction "1_1") (pintype "passive"))
    )
    (net (code "65") (name "P19") (class "Default")
      (node (ref "C32") (pin "1") (pinfunction "P$1_1") (pintype "passive"))
      (node (ref "IC2") (pin "22") (pinfunction "P0.19_22") (pintype "bidirectional"))
      (node (ref "JP11") (pin "1") (pinfunction "1_1") (pintype "passive"))
    )
    (net (code "66") (name "P23") (class "Default")
      (node (ref "IC2") (pin "28") (pinfunction "P0.23_28") (pintype "bidirectional"))
    )
    (net (code "67") (name "P24") (class "Default")
      (node (ref "IC2") (pin "29") (pinfunction "P0.24_29") (pintype "bidirectional"))
    )
    (net (code "68") (name "P28") (class "Default")
      (node (ref "IC2") (pin "40") (pinfunction "P0.28/AIN4_40") (pintype "bidirectional"))
    )
    (net (code "69") (name "PG") (class "Default")
      (node (ref "JP9") (pin "2") (pinfunction "2_2") (pintype "passive"))
      (node (ref "Q1") (pin "1") (pinfunction "G_1") (pintype "bidirectional"))
    )
    (net (code "70") (name "SCK") (class "Default")
      (node (ref "IC2") (pin "43") (pinfunction "P0.31/AIN7_43") (pintype "bidirectional"))
    )
    (net (code "71") (name "SWDCLK") (class "Default")
      (node (ref "DEBUG1") (pin "4") (pinfunction "SWDCLK/TCK_4") (pintype "bidirectional"))
      (node (ref "IC2") (pin "25") (pinfunction "SWDCLK_25") (pintype "bidirectional"))
      (node (ref "R49") (pin "2") (pinfunction "2_2") (pintype "passive"))
    )
    (net (code "72") (name "SWDIO") (class "Default")
      (node (ref "DEBUG1") (pin "2") (pinfunction "SWDIO/TMS_2") (pintype "bidirectional"))
      (node (ref "IC2") (pin "26") (pinfunction "SWDIO_26") (pintype "bidirectional"))
    )
    (net (code "73") (name "SWO{slash}TDO") (class "Default")
      (node (ref "DEBUG1") (pin "6") (pinfunction "SWO/TDO_6") (pintype "bidirectional"))
      (node (ref "IC2") (pin "21") (pinfunction "P0.18_21") (pintype "bidirectional"))
    )
    (net (code "74") (name "V-ICHG") (class "Default")
      (node (ref "C30") (pin "2") (pinfunction "P$2_2") (pintype "passive"))
      (node (ref "D1") (pin "A") (pinfunction "A_A") (pintype "passive"))
      (node (ref "JP14") (pin "2") (pinfunction "2_2") (pintype "passive"))
      (node (ref "R10") (pin "2") (pinfunction "2_2") (pintype "passive"))
    )
    (net (code "75") (name "V-VCHG") (class "Default")
      (node (ref "C7") (pin "1") (pinfunction "P$1_1") (pintype "passive"))
      (node (ref "D2") (pin "A") (pinfunction "A_A") (pintype "passive"))
      (node (ref "R11") (pin "1") (pinfunction "1_1") (pintype "passive"))
      (node (ref "R12") (pin "1") (pinfunction "1_1") (pintype "passive"))
    )
    (net (code "76") (name "VCHG") (class "Default")
      (node (ref "C4") (pin "+") (pinfunction "+_+") (pintype "passive"))
      (node (ref "JP2") (pin "3") (pinfunction "3_3") (pintype "passive"))
      (node (ref "JP3") (pin "1") (pinfunction "1_1") (pintype "passive"))
      (node (ref "JP4") (pin "1") (pinfunction "1_1") (pintype "passive"))
      (node (ref "Q3") (pin "4") (pinfunction "S2_4") (pintype "bidirectional"))
      (node (ref "R13") (pin "1") (pinfunction "1_1") (pintype "passive"))
    )
    (net (code "77") (name "VDD_BLE") (class "Default")
      (node (ref "C10") (pin "1") (pinfunction "P$1_1") (pintype "passive"))
      (node (ref "C8") (pin "1") (pinfunction "P$1_1") (pintype "passive"))
      (node (ref "C9") (pin "1") (pinfunction "P$1_1") (pintype "passive"))
      (node (ref "DEBUG1") (pin "1") (pinfunction "VCC_1") (pintype "bidirectional"))
      (node (ref "IC2") (pin "13") (pinfunction "VDD_13") (pintype "bidirectional"))
      (node (ref "IC2") (pin "36") (pinfunction "VDD_36") (pintype "bidirectional"))
      (node (ref "IC2") (pin "48") (pinfunction "VDD_48") (pintype "bidirectional"))
      (node (ref "JP13") (pin "2") (pinfunction "2_2") (pintype "passive"))
      (node (ref "JP15") (pin "1") (pinfunction "1_1") (pintype "passive"))
      (node (ref "JP17") (pin "1") (pinfunction "1_1") (pintype "passive"))
      (node (ref "L7") (pin "2") (pinfunction "2_2") (pintype "passive"))
      (node (ref "LS1") (pin "3") (pinfunction "VIN_3") (pintype "input"))
      (node (ref "LS2") (pin "3") (pinfunction "VIN_3") (pintype "input"))
      (node (ref "R6") (pin "2") (pinfunction "2_2") (pintype "passive"))
      (node (ref "R60") (pin "1") (pinfunction "1_1") (pintype "passive"))
    )
    (net (code "78") (name "VDD_MDM") (class "Default")
      (node (ref "JP17") (pin "2") (pinfunction "2_2") (pintype "passive"))
      (node (ref "LS1") (pin "1") (pinfunction "VOUT_1") (pintype "output"))
      (node (ref "UART") (pin "1") (pinfunction "1_1") (pintype "passive"))
    )
    (net (code "79") (name "VDD_SENS") (class "Default")
      (node (ref "JP15") (pin "2") (pinfunction "2_2") (pintype "passive"))
      (node (ref "LS2") (pin "1") (pinfunction "VOUT_1") (pintype "output"))
      (node (ref "SENSOR") (pin "1") (pinfunction "1_1") (pintype "passive"))
    )
    (net (code "80") (name "VDD_WPT") (class "Default")
      (node (ref "C15") (pin "1") (pinfunction "P$1_1") (pintype "passive"))
      (node (ref "D5") (pin "C") (pinfunction "C_C") (pintype "passive"))
      (node (ref "D8") (pin "C") (pinfunction "C_C") (pintype "passive"))
      (node (ref "D9") (pin "C") (pinfunction "C_C") (pintype "passive"))
      (node (ref "Q2") (pin "4") (pinfunction "S_4") (pintype "passive"))
      (node (ref "R14") (pin "1") (pinfunction "1_1") (pintype "passive"))
      (node (ref "R16") (pin "1") (pinfunction "1_1") (pintype "passive"))
      (node (ref "R8") (pin "1") (pinfunction "1_1") (pintype "passive"))
    )
    (net (code "81") (name "VIN") (class "Default")
      (node (ref "C1") (pin "1") (pinfunction "P$1_1") (pintype "passive"))
      (node (ref "IC1") (pin "1") (pinfunction "VIN_1") (pintype "power_in"))
      (node (ref "IC3") (pin "3") (pinfunction "VIN_3") (pintype "input"))
      (node (ref "Q2") (pin "1") (pinfunction "D_1") (pintype "passive"))
      (node (ref "Q2") (pin "2") (pinfunction "D_2") (pintype "passive"))
      (node (ref "Q2") (pin "5") (pinfunction "D_5") (pintype "passive"))
      (node (ref "Q2") (pin "6") (pinfunction "D_6") (pintype "passive"))
    )
    (net (code "82") (name "VMEAS") (class "Default")
      (node (ref "D3") (pin "C") (pinfunction "C_C") (pintype "passive"))
      (node (ref "JP2") (pin "1") (pinfunction "1_1") (pintype "passive"))
      (node (ref "Q3") (pin "1") (pinfunction "S1_1") (pintype "bidirectional"))
      (node (ref "R11") (pin "2") (pinfunction "2_2") (pintype "passive"))
      (node (ref "R17") (pin "1") (pinfunction "1_1") (pintype "passive"))
    )
    (net (code "83") (name "WAKE-UP") (class "Default")
      (node (ref "D4") (pin "C") (pinfunction "C_C") (pintype "passive"))
      (node (ref "JP11") (pin "2") (pinfunction "2_2") (pintype "passive"))
      (node (ref "R16") (pin "2") (pinfunction "2_2") (pintype "passive"))
    )
    (net (code "84") (name "unconnected-(DEBUG1-KEY-Pad7)") (class "Default")
      (node (ref "DEBUG1") (pin "7") (pinfunction "KEY_7") (pintype "bidirectional"))
    )
    (net (code "85") (name "unconnected-(DEBUG1-NC{slash}TDI-Pad8)") (class "Default")
      (node (ref "DEBUG1") (pin "8") (pinfunction "NC/TDI_8") (pintype "bidirectional"))
    )
    (net (code "86") (name "unconnected-(IC2-NC-Pad44)") (class "Default")
      (node (ref "IC2") (pin "44") (pinfunction "NC_44") (pintype "bidirectional"))
    )
    (net (code "87") (name "~{RESET}") (class "Default")
      (node (ref "C22") (pin "1") (pinfunction "P$1_1") (pintype "passive"))
      (node (ref "DEBUG1") (pin "10") (pinfunction "~{RESET}_10") (pintype "bidirectional"))
      (node (ref "IC2") (pin "24") (pinfunction "P0.21/RESET_24") (pintype "bidirectional"))
      (node (ref "R60") (pin "2") (pinfunction "2_2") (pintype "passive"))
    )
  )
)
